# main.net
KiCad netlist of a schematic drawn in EAGLE
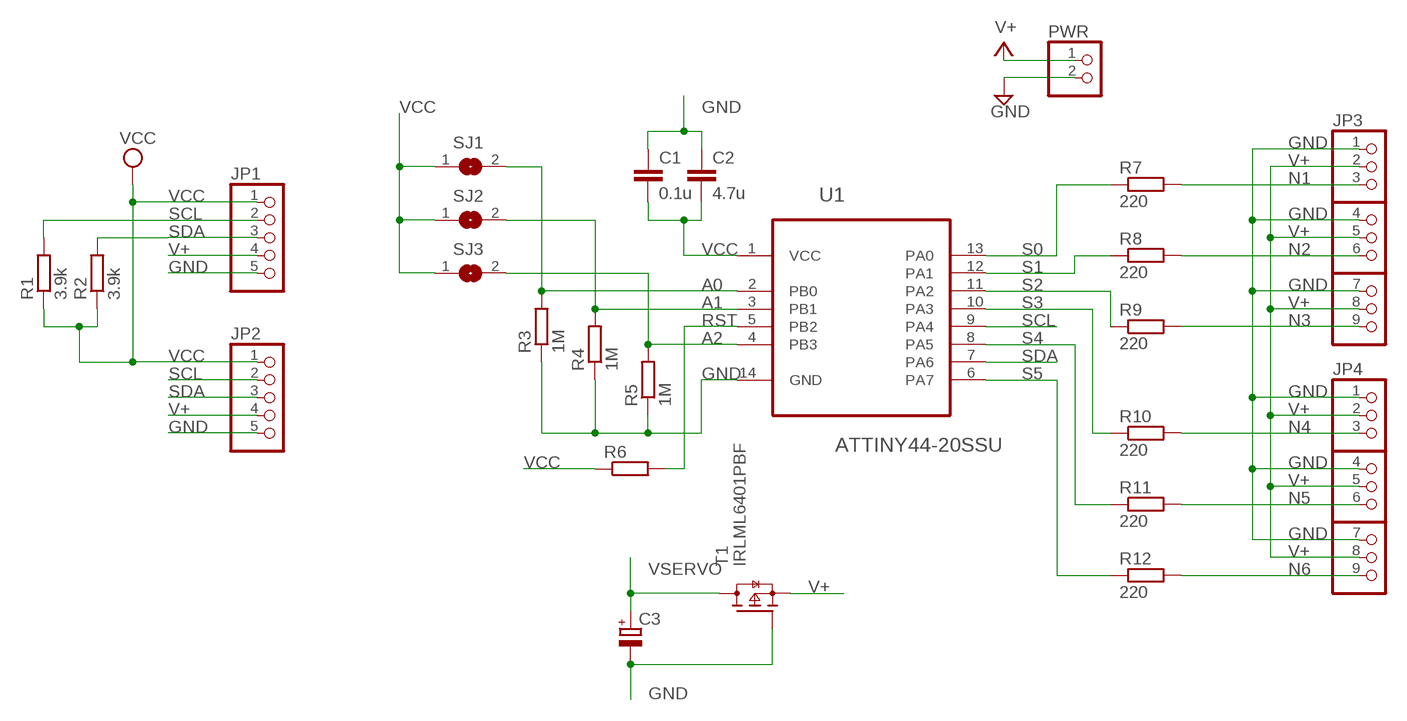
[diagram p0: schematic, sheet 1]

(export (version "E")
  (design (tool "Eeschema 10.0.6"))
  (components
    (comp (ref "C1")
      (value "0.1u")
      (footprint "eagle-import:C0805")
      (libsource (lib "eagle-import") (part "C-EUC0805"))
    )
    (comp (ref "C2")
      (value "4.7u")
      (footprint "eagle-import:C0805")
      (libsource (lib "eagle-import") (part "C-EUC0805"))
    )
    (comp (ref "C3")
      (value "CPOL-EUE2.5-6")
      (footprint "eagle-import:E2,5-6")
      (libsource (lib "eagle-import") (part "CPOL-EUE2.5-6"))
    )
    (comp (ref "JP1")
      (value "PINHD-1X5")
      (footprint "eagle-import:1X05")
      (libsource (lib "eagle-import") (part "PINHD-1X5"))
    )
    (comp (ref "JP2")
      (value "PINHD-1X5")
      (footprint "eagle-import:1X05")
      (libsource (lib "eagle-import") (part "PINHD-1X5"))
    )
    (comp (ref "JP3")
      (value "PINHD-3X3")
      (footprint "eagle-import:3X03")
      (libsource (lib "eagle-import") (part "PINHD-3X3"))
    )
    (comp (ref "JP4")
      (value "PINHD-3X3")
      (footprint "eagle-import:3X03")
      (libsource (lib "eagle-import") (part "PINHD-3X3"))
    )
    (comp (ref "PWR")
      (value "PINHD-1X2")
      (footprint "eagle-import:1X02")
      (libsource (lib "eagle-import") (part "PINHD-1X2"))
    )
    (comp (ref "R1")
      (value "3.9k")
      (footprint "eagle-import:R0805")
      (libsource (lib "eagle-import") (part "R-EU_R0805"))
    )
    (comp (ref "R2")
      (value "3.9k")
      (footprint "eagle-import:R0805")
      (libsource (lib "eagle-import") (part "R-EU_R0805"))
    )
    (comp (ref "R3")
      (value "1M")
      (footprint "eagle-import:R0805")
      (libsource (lib "eagle-import") (part "R-EU_R0805"))
    )
    (comp (ref "R4")
      (value "1M")
      (footprint "eagle-import:R0805")
      (libsource (lib "eagle-import") (part "R-EU_R0805"))
    )
    (comp (ref "R5")
      (value "1M")
      (footprint "eagle-import:R0805")
      (libsource (lib "eagle-import") (part "R-EU_R0805"))
    )
    (comp (ref "R6")
      (value "R-EU_R0805")
      (footprint "eagle-import:R0805")
      (libsource (lib "eagle-import") (part "R-EU_R0805"))
    )
    (comp (ref "R7")
      (value "220")
      (footprint "eagle-import:R0805")
      (libsource (lib "eagle-import") (part "R-EU_R0805"))
    )
    (comp (ref "R8")
      (value "220")
      (footprint "eagle-import:R0805")
      (libsource (lib "eagle-import") (part "R-EU_R0805"))
    )
    (comp (ref "R9")
      (value "220")
      (footprint "eagle-import:R0805")
      (libsource (lib "eagle-import") (part "R-EU_R0805"))
    )
    (comp (ref "R10")
      (value "220")
      (footprint "eagle-import:R0805")
      (libsource (lib "eagle-import") (part "R-EU_R0805"))
    )
    (comp (ref "R11")
      (value "220")
      (footprint "eagle-import:R0805")
      (libsource (lib "eagle-import") (part "R-EU_R0805"))
    )
    (comp (ref "R12")
      (value "220")
      (footprint "eagle-import:R0805")
      (libsource (lib "eagle-import") (part "R-EU_R0805"))
    )
    (comp (ref "SJ1") (value "SJ") (footprint "eagle-import:SJ") (libsource (lib "eagle-import") (part "SJ")))
    (comp (ref "SJ2") (value "SJ") (footprint "eagle-import:SJ") (libsource (lib "eagle-import") (part "SJ")))
    (comp (ref "SJ3") (value "SJ") (footprint "eagle-import:SJ") (libsource (lib "eagle-import") (part "SJ")))
    (comp (ref "T1")
      (value "IRLML6401PBF")
      (footprint "eagle-import:SOT23")
      (libsource (lib "eagle-import") (part "IRLML6401PBF"))
    )
    (comp (ref "U1")
      (value "ATTINY44-20SSU")
      (footprint "eagle-import:SOIC127P600X175-14N")
      (libsource (lib "eagle-import") (part "ATTINY44-20SSU"))
    )
  )
  (nets
    (net (code "1") (name "/A0") (class "Default")
      (node (ref "R3") (pin "2") (pinfunction "2_2") (pintype "passive"))
      (node (ref "SJ1") (pin "2") (pinfunction "2_2") (pintype "passive"))
      (node (ref "U1") (pin "2") (pinfunction "PB0_2") (pintype "bidirectional"))
    )
    (net (code "2") (name "/A1") (class "Default")
      (node (ref "R4") (pin "2") (pinfunction "2_2") (pintype "passive"))
      (node (ref "SJ2") (pin "2") (pinfunction "2_2") (pintype "passive"))
      (node (ref "U1") (pin "3") (pinfunction "PB1_3") (pintype "bidirectional"))
    )
    (net (code "3") (name "/A2") (class "Default")
      (node (ref "R5") (pin "2") (pinfunction "2_2") (pintype "passive"))
      (node (ref "SJ3") (pin "2") (pinfunction "2_2") (pintype "passive"))
      (node (ref "U1") (pin "4") (pinfunction "PB3_4") (pintype "bidirectional"))
    )
    (net (code "4") (name "/N1") (class "Default")
      (node (ref "JP3") (pin "3") (pinfunction "3_3") (pintype "passive"))
      (node (ref "R7") (pin "2") (pinfunction "2_2") (pintype "passive"))
    )
    (net (code "5") (name "/N2") (class "Default")
      (node (ref "JP3") (pin "6") (pinfunction "6_6") (pintype "passive"))
      (node (ref "R8") (pin "2") (pinfunction "2_2") (pintype "passive"))
    )
    (net (code "6") (name "/N3") (class "Default")
      (node (ref "JP3") (pin "9") (pinfunction "9_9") (pintype "passive"))
      (node (ref "R9") (pin "2") (pinfunction "2_2") (pintype "passive"))
    )
    (net (code "7") (name "/N4") (class "Default")
      (node (ref "JP4") (pin "3") (pinfunction "3_3") (pintype "passive"))
      (node (ref "R10") (pin "2") (pinfunction "2_2") (pintype "passive"))
    )
    (net (code "8") (name "/N5") (class "Default")
      (node (ref "JP4") (pin "6") (pinfunction "6_6") (pintype "passive"))
      (node (ref "R11") (pin "2") (pinfunction "2_2") (pintype "passive"))
    )
    (net (code "9") (name "/N6") (class "Default")
      (node (ref "JP4") (pin "9") (pinfunction "9_9") (pintype "passive"))
      (node (ref "R12") (pin "2") (pinfunction "2_2") (pintype "passive"))
    )
    (net (code "10") (name "/RST") (class "Default")
      (node (ref "R6") (pin "2") (pinfunction "2_2") (pintype "passive"))
      (node (ref "U1") (pin "5") (pinfunction "PB2_5") (pintype "bidirectional"))
    )
    (net (code "11") (name "/S0") (class "Default")
      (node (ref "R7") (pin "1") (pinfunction "1_1") (pintype "passive"))
      (node (ref "U1") (pin "13") (pinfunction "PA0_13") (pintype "bidirectional"))
    )
    (net (code "12") (name "/S1") (class "Default")
      (node (ref "R8") (pin "1") (pinfunction "1_1") (pintype "passive"))
      (node (ref "U1") (pin "12") (pinfunction "PA1_12") (pintype "bidirectional"))
    )
    (net (code "13") (name "/S2") (class "Default")
      (node (ref "R9") (pin "1") (pinfunction "1_1") (pintype "passive"))
      (node (ref "U1") (pin "11") (pinfunction "PA2_11") (pintype "bidirectional"))
    )
    (net (code "14") (name "/S3") (class "Default")
      (node (ref "R10") (pin "1") (pinfunction "1_1") (pintype "passive"))
      (node (ref "U1") (pin "10") (pinfunction "PA3_10") (pintype "bidirectional"))
    )
    (net (code "15") (name "/S4") (class "Default")
      (node (ref "R11") (pin "1") (pinfunction "1_1") (pintype "passive"))
      (node (ref "U1") (pin "8") (pinfunction "PA5_8") (pintype "bidirectional"))
    )
    (net (code "16") (name "/S5") (class "Default")
      (node (ref "R12") (pin "1") (pinfunction "1_1") (pintype "passive"))
      (node (ref "U1") (pin "6") (pinfunction "PA7_6") (pintype "bidirectional"))
    )
    (net (code "17") (name "/SCL") (class "Default")
      (node (ref "JP1") (pin "2") (pinfunction "2_2") (pintype "passive"))
      (node (ref "JP2") (pin "2") (pinfunction "2_2") (pintype "passive"))
      (node (ref "R1") (pin "2") (pinfunction "2_2") (pintype "passive"))
      (node (ref "U1") (pin "9") (pinfunction "PA4_9") (pintype "bidirectional"))
    )
    (net (code "18") (name "/SDA") (class "Default")
      (node (ref "JP1") (pin "3") (pinfunction "3_3") (pintype "passive"))
      (node (ref "JP2") (pin "3") (pinfunction "3_3") (pintype "passive"))
      (node (ref "R2") (pin "2") (pinfunction "2_2") (pintype "passive"))
      (node (ref "U1") (pin "7") (pinfunction "PA6_7") (pintype "bidirectional"))
    )
    (net (code "19") (name "/VSERVO") (class "Default")
      (node (ref "C3") (pin "+") (pinfunction "+_+") (pintype "passive"))
      (node (ref "T1") (pin "3") (pinfunction "D_3") (pintype "passive"))
    )
    (net (code "20") (name "GND") (class "Default")
      (node (ref "C1") (pin "1") (pinfunction "1_1") (pintype "passive"))
      (node (ref "C2") (pin "1") (pinfunction "1_1") (pintype "passive"))
      (node (ref "C3") (pin "-") (pinfunction "-_-") (pintype "passive"))
      (node (ref "JP1") (pin "5") (pinfunction "5_5") (pintype "passive"))
      (node (ref "JP2") (pin "5") (pinfunction "5_5") (pintype "passive"))
      (node (ref "JP3") (pin "1") (pinfunction "1_1") (pintype "passive"))
      (node (ref "JP3") (pin "4") (pinfunction "4_4") (pintype "passive"))
      (node (ref "JP3") (pin "7") (pinfunction "7_7") (pintype "passive"))
      (node (ref "JP4") (pin "1") (pinfunction "1_1") (pintype "passive"))
      (node (ref "JP4") (pin "4") (pinfunction "4_4") (pintype "passive"))
      (node (ref "JP4") (pin "7") (pinfunction "7_7") (pintype "passive"))
      (node (ref "PWR") (pin "2") (pinfunction "2_2") (pintype "passive"))
      (node (ref "R3") (pin "1") (pinfunction "1_1") (pintype "passive"))
      (node (ref "R4") (pin "1") (pinfunction "1_1") (pintype "passive"))
      (node (ref "R5") (pin "1") (pinfunction "1_1") (pintype "passive"))
      (node (ref "T1") (pin "1") (pinfunction "G_1") (pintype "passive"))
      (node (ref "U1") (pin "14") (pinfunction "GND_14") (pintype "passive"))
    )
    (net (code "21") (name "V+") (class "Default")
      (node (ref "JP1") (pin "4") (pinfunction "4_4") (pintype "passive"))
      (node (ref "JP2") (pin "4") (pinfunction "4_4") (pintype "passive"))
      (node (ref "JP3") (pin "2") (pinfunction "2_2") (pintype "passive"))
      (node (ref "JP3") (pin "5") (pinfunction "5_5") (pintype "passive"))
      (node (ref "JP3") (pin "8") (pinfunction "8_8") (pintype "passive"))
      (node (ref "JP4") (pin "2") (pinfunction "2_2") (pintype "passive"))
      (node (ref "JP4") (pin "5") (pinfunction "5_5") (pintype "passive"))
      (node (ref "JP4") (pin "8") (pinfunction "8_8") (pintype "passive"))
      (node (ref "PWR") (pin "1") (pinfunction "1_1") (pintype "passive"))
      (node (ref "T1") (pin "2") (pinfunction "S_2") (pintype "passive"))
    )
    (net (code "22") (name "VCC") (class "Default")
      (node (ref "C1") (pin "2") (pinfunction "2_2") (pintype "passive"))
      (node (ref "C2") (pin "2") (pinfunction "2_2") (pintype "passive"))
      (node (ref "JP1") (pin "1") (pinfunction "1_1") (pintype "passive"))
      (node (ref "JP2") (pin "1") (pinfunction "1_1") (pintype "passive"))
      (node (ref "R1") (pin "1") (pinfunction "1_1") (pintype "passive"))
      (node (ref "R2") (pin "1") (pinfunction "1_1") (pintype "passive"))
      (node (ref "R6") (pin "1") (pinfunction "1_1") (pintype "passive"))
      (node (ref "SJ1") (pin "1") (pinfunction "1_1") (pintype "passive"))
      (node (ref "SJ2") (pin "1") (pinfunction "1_1") (pintype "passive"))
      (node (ref "SJ3") (pin "1") (pinfunction "1_1") (pintype "passive"))
      (node (ref "U1") (pin "1") (pinfunction "VCC_1") (pintype "power_in"))
    )
  )
)
